# single44.net
KiCad netlist of a schematic drawn in EAGLE
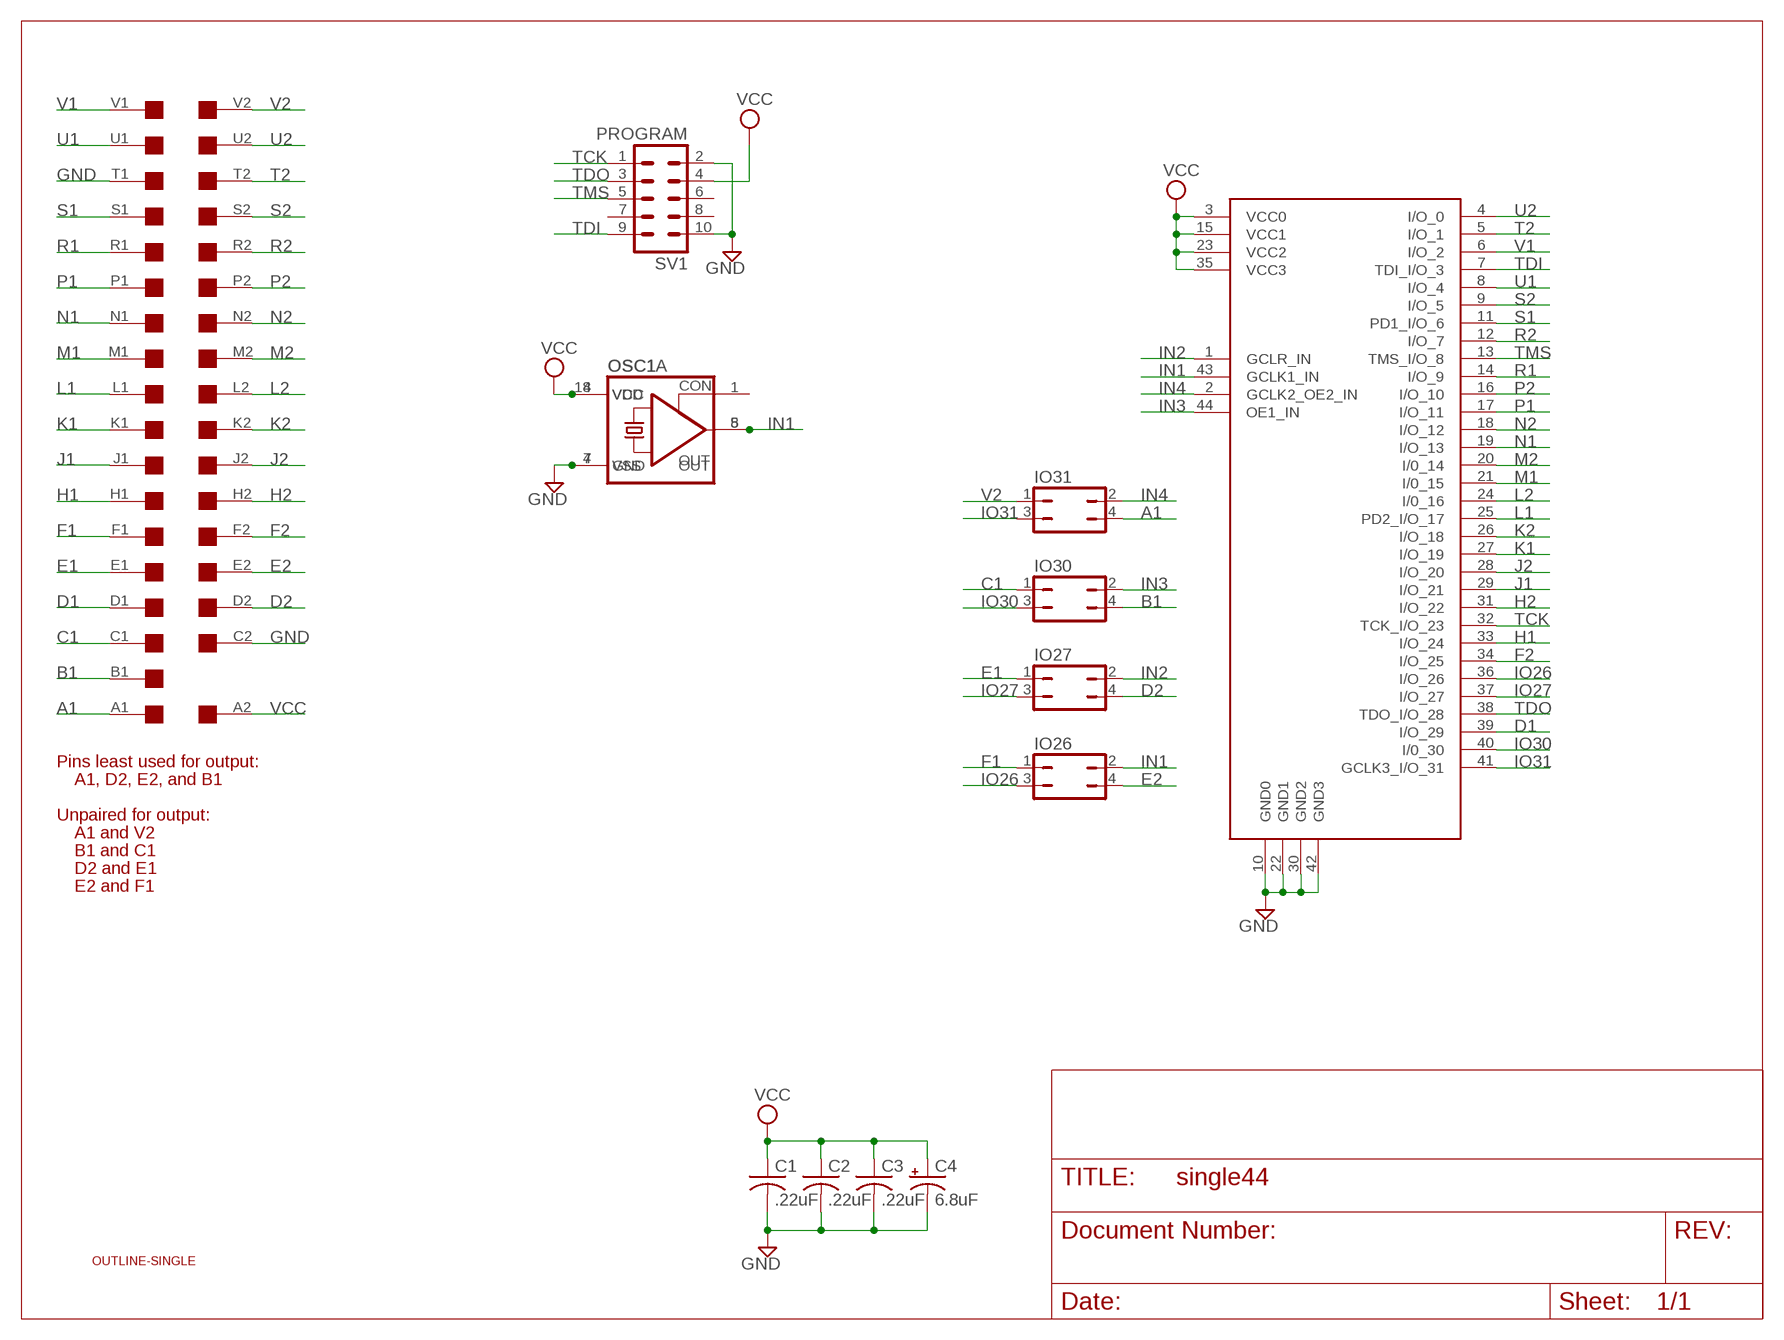
[diagram p0: schematic, sheet 1]

(export (version "E")
  (design (tool "Eeschema 10.0.6"))
  (components
    (comp (ref "C1")
      (value ".22uF")
      (footprint "eagle-import:C050-025X075")
      (libsource (lib "eagle-import") (part "C-US050-025X075"))
    )
    (comp (ref "C2")
      (value ".22uF")
      (footprint "eagle-import:C050-025X075")
      (libsource (lib "eagle-import") (part "C-US050-025X075"))
    )
    (comp (ref "C3")
      (value ".22uF")
      (footprint "eagle-import:C050-025X075")
      (libsource (lib "eagle-import") (part "C-US050-025X075"))
    )
    (comp (ref "C4")
      (value "6.8uF")
      (footprint "eagle-import:E15-5")
      (libsource (lib "eagle-import") (part "CPOL-USE15-5AXIAL"))
    )
    (comp (ref "IO26")
      (value "JP2Q")
      (footprint "eagle-import:JP2Q")
      (libsource (lib "eagle-import") (part "JP2Q"))
    )
    (comp (ref "IO27")
      (value "JP2Q")
      (footprint "eagle-import:JP2Q")
      (libsource (lib "eagle-import") (part "JP2Q"))
    )
    (comp (ref "IO30")
      (value "JP2Q")
      (footprint "eagle-import:JP2Q")
      (libsource (lib "eagle-import") (part "JP2Q"))
    )
    (comp (ref "IO31")
      (value "JP2Q")
      (footprint "eagle-import:JP2Q")
      (libsource (lib "eagle-import") (part "JP2Q"))
    )
    (comp (ref "OSC1")
      (value "QG5460")
      (footprint "eagle-import:DIL08S")
      (libsource (lib "eagle-import") (part "QG5460"))
    )
    (comp (ref "OSC1A")
      (value "CRYSTAL_RES-SG51")
      (footprint "eagle-import:SG51")
      (libsource (lib "eagle-import") (part "CRYSTAL_RES-SG51"))
    )
    (comp (ref "SV1")
      (value "PROGRAM")
      (footprint "eagle-import:ML10")
      (libsource (lib "eagle-import") (part "ML10"))
    )
    (comp (ref "U$1")
      (value "OUTLINE-SINGLE")
      (footprint "eagle-import:SINGLE")
      (libsource (lib "eagle-import") (part "OUTLINE-SINGLE"))
    )
    (comp (ref "U$2")
      (value "SINGLE")
      (footprint "eagle-import:EDGE-CON2")
      (libsource (lib "eagle-import") (part "SINGLE"))
    )
    (comp (ref "U1")
      (value "ATF1504")
      (footprint "eagle-import:3M44")
      (libsource (lib "eagle-import") (part "ATF1502PLCC44"))
    )
  )
  (nets
    (net (code "1") (name "/A1") (class "Default")
      (node (ref "IO31") (pin "4") (pinfunction "4_4") (pintype "passive"))
      (node (ref "U$2") (pin "A1") (pinfunction "1_A1") (pintype "bidirectional"))
    )
    (net (code "2") (name "/B1") (class "Default")
      (node (ref "IO30") (pin "4") (pinfunction "4_4") (pintype "passive"))
      (node (ref "U$2") (pin "B1") (pinfunction "1_B1") (pintype "bidirectional"))
    )
    (net (code "3") (name "/C1") (class "Default")
      (node (ref "IO30") (pin "1") (pinfunction "1_1") (pintype "passive"))
      (node (ref "U$2") (pin "C1") (pinfunction "1_C1") (pintype "bidirectional"))
    )
    (net (code "4") (name "/D1") (class "Default")
      (node (ref "U$2") (pin "D1") (pinfunction "1_D1") (pintype "bidirectional"))
      (node (ref "U1") (pin "39") (pinfunction "I/O_29_39") (pintype "bidirectional"))
    )
    (net (code "5") (name "/D2") (class "Default")
      (node (ref "IO27") (pin "4") (pinfunction "4_4") (pintype "passive"))
      (node (ref "U$2") (pin "D2") (pinfunction "1_D2") (pintype "bidirectional"))
    )
    (net (code "6") (name "/E1") (class "Default")
      (node (ref "IO27") (pin "1") (pinfunction "1_1") (pintype "passive"))
      (node (ref "U$2") (pin "E1") (pinfunction "1_E1") (pintype "bidirectional"))
    )
    (net (code "7") (name "/E2") (class "Default")
      (node (ref "IO26") (pin "4") (pinfunction "4_4") (pintype "passive"))
      (node (ref "U$2") (pin "E2") (pinfunction "1_E2") (pintype "bidirectional"))
    )
    (net (code "8") (name "/F1") (class "Default")
      (node (ref "IO26") (pin "1") (pinfunction "1_1") (pintype "passive"))
      (node (ref "U$2") (pin "F1") (pinfunction "1_F1") (pintype "bidirectional"))
    )
    (net (code "9") (name "/F2") (class "Default")
      (node (ref "U$2") (pin "F2") (pinfunction "1_F2") (pintype "bidirectional"))
      (node (ref "U1") (pin "34") (pinfunction "I/O_25_34") (pintype "bidirectional"))
    )
    (net (code "10") (name "/H1") (class "Default")
      (node (ref "U$2") (pin "H1") (pinfunction "1_H1") (pintype "bidirectional"))
      (node (ref "U1") (pin "33") (pinfunction "I/O_24_33") (pintype "bidirectional"))
    )
    (net (code "11") (name "/H2") (class "Default")
      (node (ref "U$2") (pin "H2") (pinfunction "1_H2") (pintype "bidirectional"))
      (node (ref "U1") (pin "31") (pinfunction "I/O_22_31") (pintype "bidirectional"))
    )
    (net (code "12") (name "/IN1") (class "Default")
      (node (ref "IO26") (pin "2") (pinfunction "2_2") (pintype "passive"))
      (node (ref "OSC1") (pin "5") (pinfunction "OUT_5") (pintype "output"))
      (node (ref "OSC1A") (pin "8") (pinfunction "OUT_8") (pintype "output"))
      (node (ref "U1") (pin "43") (pinfunction "GCLK1_IN_43") (pintype "bidirectional"))
    )
    (net (code "13") (name "/IN2") (class "Default")
      (node (ref "IO27") (pin "2") (pinfunction "2_2") (pintype "passive"))
      (node (ref "U1") (pin "1") (pinfunction "GCLR_IN_1") (pintype "bidirectional"))
    )
    (net (code "14") (name "/IN3") (class "Default")
      (node (ref "IO30") (pin "2") (pinfunction "2_2") (pintype "passive"))
      (node (ref "U1") (pin "44") (pinfunction "OE1_IN_44") (pintype "bidirectional"))
    )
    (net (code "15") (name "/IN4") (class "Default")
      (node (ref "IO31") (pin "2") (pinfunction "2_2") (pintype "passive"))
      (node (ref "U1") (pin "2") (pinfunction "GCLK2_OE2_IN_2") (pintype "bidirectional"))
    )
    (net (code "16") (name "/IO26") (class "Default")
      (node (ref "IO26") (pin "3") (pinfunction "3_3") (pintype "passive"))
      (node (ref "U1") (pin "36") (pinfunction "I/O_26_36") (pintype "bidirectional"))
    )
    (net (code "17") (name "/IO27") (class "Default")
      (node (ref "IO27") (pin "3") (pinfunction "3_3") (pintype "passive"))
      (node (ref "U1") (pin "37") (pinfunction "I/O_27_37") (pintype "bidirectional"))
    )
    (net (code "18") (name "/IO30") (class "Default")
      (node (ref "IO30") (pin "3") (pinfunction "3_3") (pintype "passive"))
      (node (ref "U1") (pin "40") (pinfunction "I/0_30_40") (pintype "bidirectional"))
    )
    (net (code "19") (name "/IO31") (class "Default")
      (node (ref "IO31") (pin "3") (pinfunction "3_3") (pintype "passive"))
      (node (ref "U1") (pin "41") (pinfunction "GCLK3_I/O_31_41") (pintype "bidirectional"))
    )
    (net (code "20") (name "/J1") (class "Default")
      (node (ref "U$2") (pin "J1") (pinfunction "1_J1") (pintype "bidirectional"))
      (node (ref "U1") (pin "29") (pinfunction "I/O_21_29") (pintype "bidirectional"))
    )
    (net (code "21") (name "/J2") (class "Default")
      (node (ref "U$2") (pin "J2") (pinfunction "1_J2") (pintype "bidirectional"))
      (node (ref "U1") (pin "28") (pinfunction "I/O_20_28") (pintype "bidirectional"))
    )
    (net (code "22") (name "/K1") (class "Default")
      (node (ref "U$2") (pin "K1") (pinfunction "1_K1") (pintype "bidirectional"))
      (node (ref "U1") (pin "27") (pinfunction "I/O_19_27") (pintype "bidirectional"))
    )
    (net (code "23") (name "/K2") (class "Default")
      (node (ref "U$2") (pin "K2") (pinfunction "1_K2") (pintype "bidirectional"))
      (node (ref "U1") (pin "26") (pinfunction "I/O_18_26") (pintype "bidirectional"))
    )
    (net (code "24") (name "/L1") (class "Default")
      (node (ref "U$2") (pin "L1") (pinfunction "1_L1") (pintype "bidirectional"))
      (node (ref "U1") (pin "25") (pinfunction "PD2_I/O_17_25") (pintype "bidirectional"))
    )
    (net (code "25") (name "/L2") (class "Default")
      (node (ref "U$2") (pin "L2") (pinfunction "1_L2") (pintype "bidirectional"))
      (node (ref "U1") (pin "24") (pinfunction "I/0_16_24") (pintype "bidirectional"))
    )
    (net (code "26") (name "/M1") (class "Default")
      (node (ref "U$2") (pin "M1") (pinfunction "1_M1") (pintype "bidirectional"))
      (node (ref "U1") (pin "21") (pinfunction "I/0_15_21") (pintype "bidirectional"))
    )
    (net (code "27") (name "/M2") (class "Default")
      (node (ref "U$2") (pin "M2") (pinfunction "1_M2") (pintype "bidirectional"))
      (node (ref "U1") (pin "20") (pinfunction "I/0_14_20") (pintype "bidirectional"))
    )
    (net (code "28") (name "/N1") (class "Default")
      (node (ref "U$2") (pin "N1") (pinfunction "1_N1") (pintype "bidirectional"))
      (node (ref "U1") (pin "19") (pinfunction "I/O_13_19") (pintype "bidirectional"))
    )
    (net (code "29") (name "/N2") (class "Default")
      (node (ref "U$2") (pin "N2") (pinfunction "1_N2") (pintype "bidirectional"))
      (node (ref "U1") (pin "18") (pinfunction "I/O_12_18") (pintype "bidirectional"))
    )
    (net (code "30") (name "/P1") (class "Default")
      (node (ref "U$2") (pin "P1") (pinfunction "1_P1") (pintype "bidirectional"))
      (node (ref "U1") (pin "17") (pinfunction "I/O_11_17") (pintype "bidirectional"))
    )
    (net (code "31") (name "/P2") (class "Default")
      (node (ref "U$2") (pin "P2") (pinfunction "1_P2") (pintype "bidirectional"))
      (node (ref "U1") (pin "16") (pinfunction "I/O_10_16") (pintype "bidirectional"))
    )
    (net (code "32") (name "/R1") (class "Default")
      (node (ref "U$2") (pin "R1") (pinfunction "1_R1") (pintype "bidirectional"))
      (node (ref "U1") (pin "14") (pinfunction "I/O_9_14") (pintype "bidirectional"))
    )
    (net (code "33") (name "/R2") (class "Default")
      (node (ref "U$2") (pin "R2") (pinfunction "1_R2") (pintype "bidirectional"))
      (node (ref "U1") (pin "12") (pinfunction "I/O_7_12") (pintype "bidirectional"))
    )
    (net (code "34") (name "/S1") (class "Default")
      (node (ref "U$2") (pin "S1") (pinfunction "1_S1") (pintype "bidirectional"))
      (node (ref "U1") (pin "11") (pinfunction "PD1_I/O_6_11") (pintype "bidirectional"))
    )
    (net (code "35") (name "/S2") (class "Default")
      (node (ref "U$2") (pin "S2") (pinfunction "1_S2") (pintype "bidirectional"))
      (node (ref "U1") (pin "9") (pinfunction "I/O_5_9") (pintype "bidirectional"))
    )
    (net (code "36") (name "/T2") (class "Default")
      (node (ref "U$2") (pin "T2") (pinfunction "1_T2") (pintype "bidirectional"))
      (node (ref "U1") (pin "5") (pinfunction "I/O_1_5") (pintype "bidirectional"))
    )
    (net (code "37") (name "/TCK") (class "Default")
      (node (ref "SV1") (pin "1") (pinfunction "1_1") (pintype "passive"))
      (node (ref "U1") (pin "32") (pinfunction "TCK_I/O_23_32") (pintype "bidirectional"))
    )
    (net (code "38") (name "/TDI") (class "Default")
      (node (ref "SV1") (pin "9") (pinfunction "9_9") (pintype "passive"))
      (node (ref "U1") (pin "7") (pinfunction "TDI_I/O_3_7") (pintype "bidirectional"))
    )
    (net (code "39") (name "/TDO") (class "Default")
      (node (ref "SV1") (pin "3") (pinfunction "3_3") (pintype "passive"))
      (node (ref "U1") (pin "38") (pinfunction "TDO_I/O_28_38") (pintype "bidirectional"))
    )
    (net (code "40") (name "/TMS") (class "Default")
      (node (ref "SV1") (pin "5") (pinfunction "5_5") (pintype "passive"))
      (node (ref "U1") (pin "13") (pinfunction "TMS_I/O_8_13") (pintype "bidirectional"))
    )
    (net (code "41") (name "/U1") (class "Default")
      (node (ref "U$2") (pin "U1") (pinfunction "1_U1") (pintype "bidirectional"))
      (node (ref "U1") (pin "8") (pinfunction "I/O_4_8") (pintype "bidirectional"))
    )
    (net (code "42") (name "/U2") (class "Default")
      (node (ref "U$2") (pin "U2") (pinfunction "1_U2") (pintype "bidirectional"))
      (node (ref "U1") (pin "4") (pinfunction "I/O_0_4") (pintype "bidirectional"))
    )
    (net (code "43") (name "/V1") (class "Default")
      (node (ref "U$2") (pin "V1") (pinfunction "1_V1") (pintype "bidirectional"))
      (node (ref "U1") (pin "6") (pinfunction "I/O_2_6") (pintype "bidirectional"))
    )
    (net (code "44") (name "/V2") (class "Default")
      (node (ref "IO31") (pin "1") (pinfunction "1_1") (pintype "passive"))
      (node (ref "U$2") (pin "V2") (pinfunction "1_V2") (pintype "bidirectional"))
    )
    (net (code "45") (name "GND") (class "Default")
      (node (ref "C1") (pin "2") (pinfunction "2_2") (pintype "passive"))
      (node (ref "C2") (pin "2") (pinfunction "2_2") (pintype "passive"))
      (node (ref "C3") (pin "2") (pinfunction "2_2") (pintype "passive"))
      (node (ref "C4") (pin "-") (pinfunction "-_-") (pintype "passive"))
      (node (ref "OSC1") (pin "4") (pinfunction "GND_4") (pintype "power_in"))
      (node (ref "OSC1A") (pin "7") (pinfunction "VSS_7") (pintype "power_in"))
      (node (ref "SV1") (pin "10") (pinfunction "10_10") (pintype "passive"))
      (node (ref "SV1") (pin "2") (pinfunction "2_2") (pintype "passive"))
      (node (ref "U$2") (pin "C2") (pinfunction "1_C2") (pintype "bidirectional"))
      (node (ref "U$2") (pin "T1") (pinfunction "1_T1") (pintype "bidirectional"))
      (node (ref "U1") (pin "10") (pinfunction "GND0_10") (pintype "bidirectional"))
      (node (ref "U1") (pin "22") (pinfunction "GND1_22") (pintype "bidirectional"))
      (node (ref "U1") (pin "30") (pinfunction "GND2_30") (pintype "bidirectional"))
      (node (ref "U1") (pin "42") (pinfunction "GND3_42") (pintype "bidirectional"))
    )
    (net (code "46") (name "VCC") (class "Default")
      (node (ref "C1") (pin "1") (pinfunction "1_1") (pintype "passive"))
      (node (ref "C2") (pin "1") (pinfunction "1_1") (pintype "passive"))
      (node (ref "C3") (pin "1") (pinfunction "1_1") (pintype "passive"))
      (node (ref "C4") (pin "+") (pinfunction "+_+") (pintype "passive"))
      (node (ref "OSC1") (pin "8") (pinfunction "VCC_8") (pintype "power_in"))
      (node (ref "OSC1A") (pin "14") (pinfunction "VDD_14") (pintype "power_in"))
      (node (ref "SV1") (pin "4") (pinfunction "4_4") (pintype "passive"))
      (node (ref "U$2") (pin "A2") (pinfunction "1_A2") (pintype "bidirectional"))
      (node (ref "U1") (pin "15") (pinfunction "VCC1_15") (pintype "bidirectional"))
      (node (ref "U1") (pin "23") (pinfunction "VCC2_23") (pintype "bidirectional"))
      (node (ref "U1") (pin "3") (pinfunction "VCC0_3") (pintype "bidirectional"))
      (node (ref "U1") (pin "35") (pinfunction "VCC3_35") (pintype "bidirectional"))
    )
    (net (code "47") (name "unconnected-(OSC1A-CON-Pad1)") (class "Default")
      (node (ref "OSC1A") (pin "1") (pinfunction "CON_1") (pintype "input"))
    )
    (net (code "48") (name "unconnected-(SV1-Pad6)") (class "Default")
      (node (ref "SV1") (pin "6") (pinfunction "6_6") (pintype "passive"))
    )
    (net (code "49") (name "unconnected-(SV1-Pad7)") (class "Default")
      (node (ref "SV1") (pin "7") (pinfunction "7_7") (pintype "passive"))
    )
    (net (code "50") (name "unconnected-(SV1-Pad8)") (class "Default")
      (node (ref "SV1") (pin "8") (pinfunction "8_8") (pintype "passive"))
    )
  )
)
